# ESP_IAQ_baseBoard.net
KiCad netlist of a schematic drawn in EAGLE
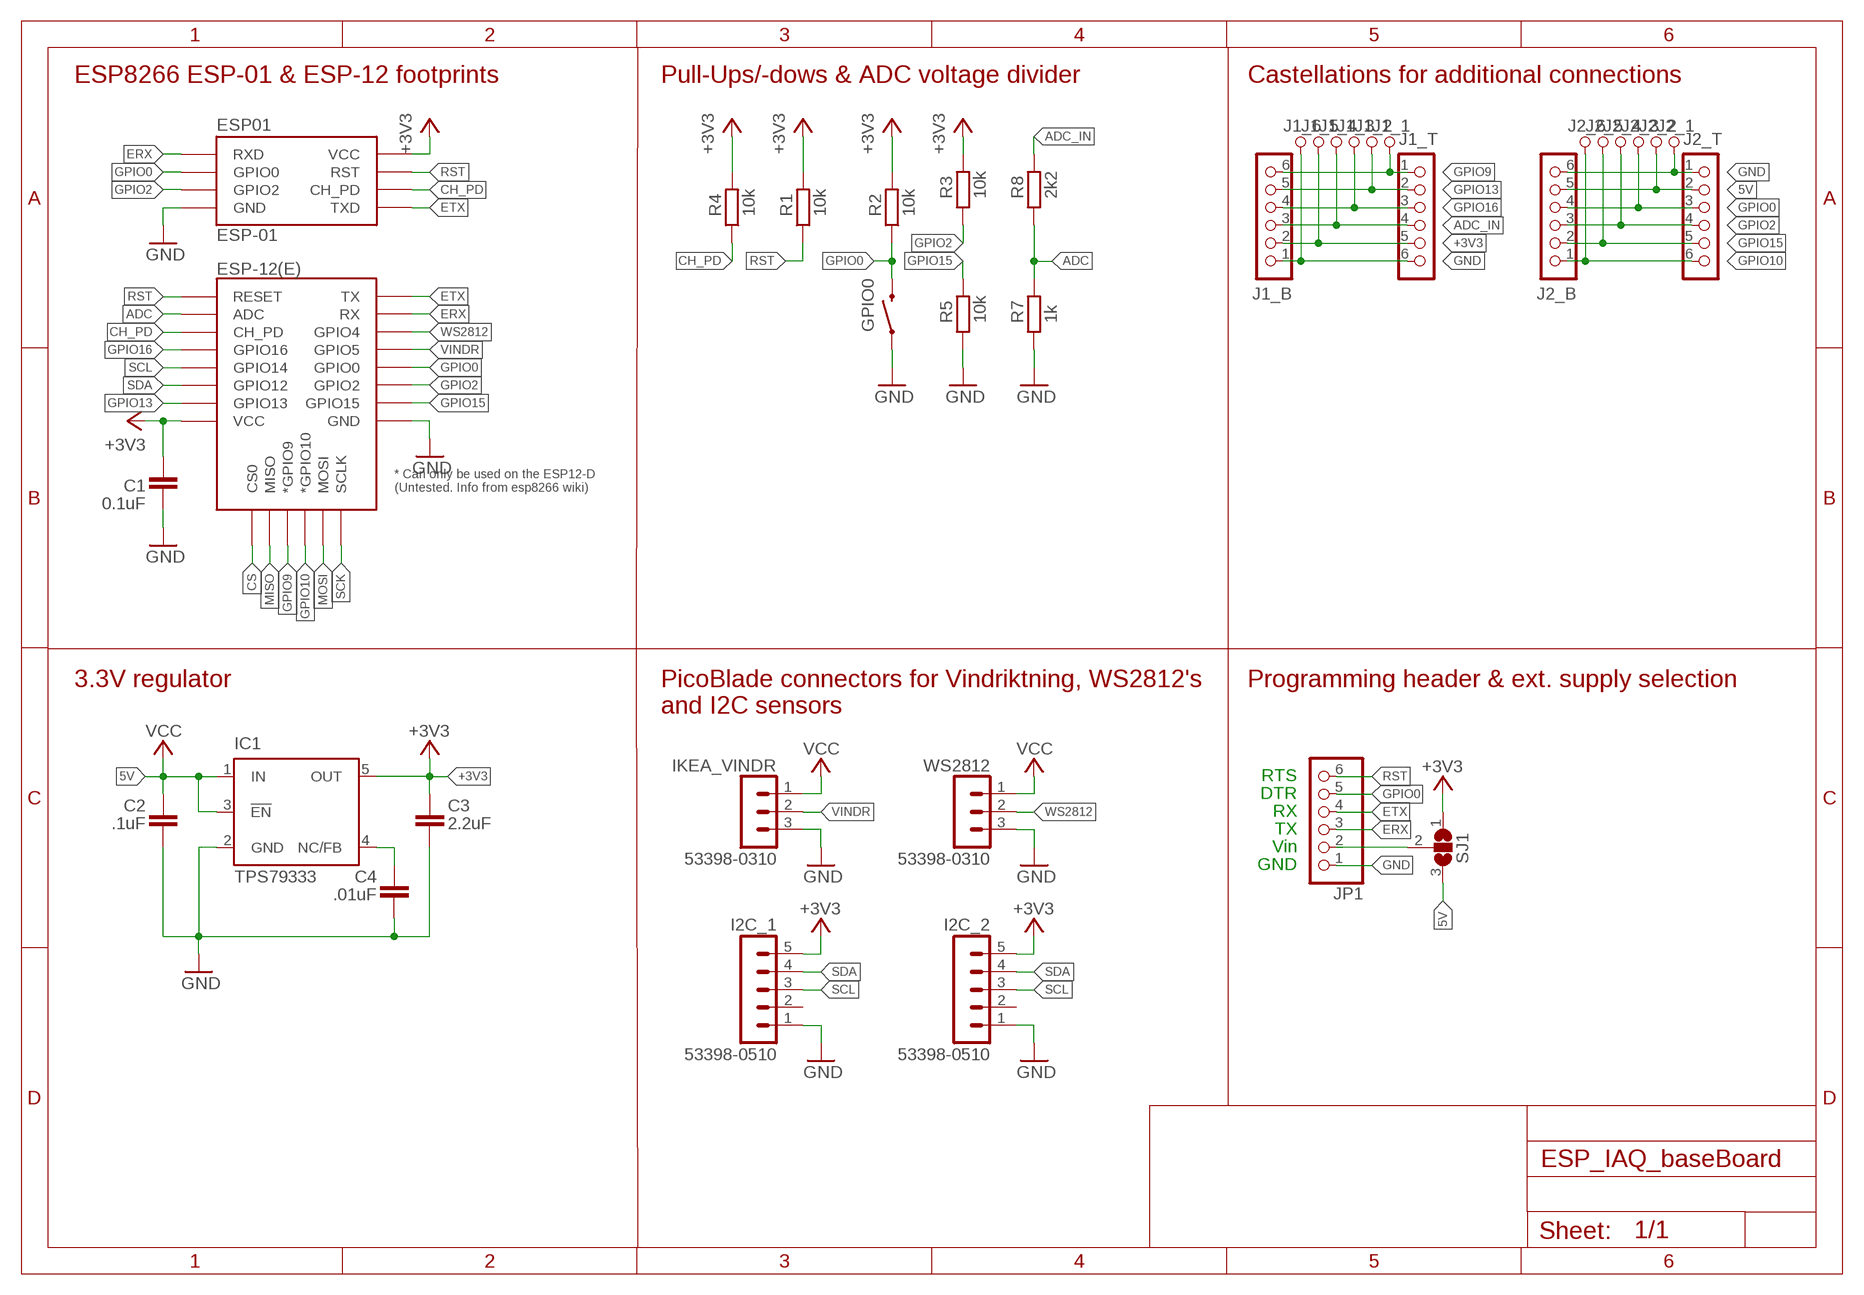
[diagram p0: schematic, sheet 1]

(export (version "E")
  (design (tool "Eeschema 10.0.6"))
  (components
    (comp (ref "C1")
      (value "0.1uF")
      (footprint "eagle-import:C805")
      (libsource (lib "eagle-import") (part "CAPACITOR_NPOL-0805"))
    )
    (comp (ref "C2")
      (value ".1uF")
      (footprint "eagle-import:C805")
      (libsource (lib "eagle-import") (part "CAPACITOR_NPOL-0805"))
    )
    (comp (ref "C3")
      (value "2.2uF")
      (footprint "eagle-import:C805")
      (libsource (lib "eagle-import") (part "CAPACITOR_NPOL-0805"))
    )
    (comp (ref "C4")
      (value ".01uF")
      (footprint "eagle-import:C805")
      (libsource (lib "eagle-import") (part "CAPACITOR_NPOL-0805"))
    )
    (comp (ref "ESP-01")
      (value "ESP01")
      (footprint "eagle-import:ESP01")
      (libsource (lib "eagle-import") (part "ESP01"))
    )
    (comp (ref "ESP-12(E)")
      (value "ESP12ESMD")
      (footprint "eagle-import:ESP12E-SMD")
      (libsource (lib "eagle-import") (part "ESP12ESMD"))
    )
    (comp (ref "GPIO0")
      (value "MOMENTARY-SWITCH-SPST-SMD-RIGHT-ANGLE")
      (footprint "eagle-import:TACTILE_SWITCH_SMD_RIGHT_ANGLE")
      (libsource (lib "eagle-import") (part "MOMENTARY-SWITCH-SPST-SMD-RIGHT-ANGLE"))
    )
    (comp (ref "I2C_1")
      (value "53398-0510")
      (footprint "eagle-import:53398-0510")
      (libsource (lib "eagle-import") (part "53398-0510"))
    )
    (comp (ref "I2C_2")
      (value "53398-0510")
      (footprint "eagle-import:53398-0510")
      (libsource (lib "eagle-import") (part "53398-0510"))
    )
    (comp (ref "IC1")
      (value "TPS79333")
      (footprint "eagle-import:SOT23-DBV")
      (fields (field (name "MF") "TEXAS INSTRUMENTS") (field (name "MPN") "TPS77033DBVT"))
      (libsource (lib "eagle-import") (part "TPS77033"))
    )
    (comp (ref "IKEA_VINDR")
      (value "53398-0310")
      (footprint "eagle-import:53398-0310")
      (libsource (lib "eagle-import") (part "53398-0310"))
    )
    (comp (ref "J1_1")
      (value "PAD_TERMINAL-1.02MM_ROUND")
      (footprint "eagle-import:CON_PAD_ROUND_1.02MM")
      (libsource (lib "eagle-import") (part "PAD_TERMINAL-1.02MM_ROUND"))
    )
    (comp (ref "J1_2")
      (value "PAD_TERMINAL-1.02MM_ROUND")
      (footprint "eagle-import:CON_PAD_ROUND_1.02MM")
      (libsource (lib "eagle-import") (part "PAD_TERMINAL-1.02MM_ROUND"))
    )
    (comp (ref "J1_3")
      (value "PAD_TERMINAL-1.02MM_ROUND")
      (footprint "eagle-import:CON_PAD_ROUND_1.02MM")
      (libsource (lib "eagle-import") (part "PAD_TERMINAL-1.02MM_ROUND"))
    )
    (comp (ref "J1_4")
      (value "PAD_TERMINAL-1.02MM_ROUND")
      (footprint "eagle-import:CON_PAD_ROUND_1.02MM")
      (libsource (lib "eagle-import") (part "PAD_TERMINAL-1.02MM_ROUND"))
    )
    (comp (ref "J1_5")
      (value "PAD_TERMINAL-1.02MM_ROUND")
      (footprint "eagle-import:CON_PAD_ROUND_1.02MM")
      (libsource (lib "eagle-import") (part "PAD_TERMINAL-1.02MM_ROUND"))
    )
    (comp (ref "J1_6")
      (value "PAD_TERMINAL-1.02MM_ROUND")
      (footprint "eagle-import:CON_PAD_ROUND_1.02MM")
      (libsource (lib "eagle-import") (part "PAD_TERMINAL-1.02MM_ROUND"))
    )
    (comp (ref "J1_B")
      (value "CON_HEADER_1X06-SMD-RIGHT-ANGLED")
      (footprint "eagle-import:M1X6_MALE_RIGHT_ANGLED_SMD")
      (libsource (lib "eagle-import") (part "CON_HEADER_1X06-SMD-RIGHT-ANGLED"))
    )
    (comp (ref "J1_T")
      (value "CON_HEADER_1X06-SMD-RIGHT-ANGLED")
      (footprint "eagle-import:M1X6_MALE_RIGHT_ANGLED_SMD")
      (libsource (lib "eagle-import") (part "CON_HEADER_1X06-SMD-RIGHT-ANGLED"))
    )
    (comp (ref "J2_1")
      (value "PAD_TERMINAL-1.02MM_ROUND")
      (footprint "eagle-import:CON_PAD_ROUND_1.02MM")
      (libsource (lib "eagle-import") (part "PAD_TERMINAL-1.02MM_ROUND"))
    )
    (comp (ref "J2_2")
      (value "PAD_TERMINAL-1.02MM_ROUND")
      (footprint "eagle-import:CON_PAD_ROUND_1.02MM")
      (libsource (lib "eagle-import") (part "PAD_TERMINAL-1.02MM_ROUND"))
    )
    (comp (ref "J2_3")
      (value "PAD_TERMINAL-1.02MM_ROUND")
      (footprint "eagle-import:CON_PAD_ROUND_1.02MM")
      (libsource (lib "eagle-import") (part "PAD_TERMINAL-1.02MM_ROUND"))
    )
    (comp (ref "J2_4")
      (value "PAD_TERMINAL-1.02MM_ROUND")
      (footprint "eagle-import:CON_PAD_ROUND_1.02MM")
      (libsource (lib "eagle-import") (part "PAD_TERMINAL-1.02MM_ROUND"))
    )
    (comp (ref "J2_5")
      (value "PAD_TERMINAL-1.02MM_ROUND")
      (footprint "eagle-import:CON_PAD_ROUND_1.02MM")
      (libsource (lib "eagle-import") (part "PAD_TERMINAL-1.02MM_ROUND"))
    )
    (comp (ref "J2_6")
      (value "PAD_TERMINAL-1.02MM_ROUND")
      (footprint "eagle-import:CON_PAD_ROUND_1.02MM")
      (libsource (lib "eagle-import") (part "PAD_TERMINAL-1.02MM_ROUND"))
    )
    (comp (ref "J2_B")
      (value "CON_HEADER_1X06-SMD-RIGHT-ANGLED")
      (footprint "eagle-import:M1X6_MALE_RIGHT_ANGLED_SMD")
      (libsource (lib "eagle-import") (part "CON_HEADER_1X06-SMD-RIGHT-ANGLED"))
    )
    (comp (ref "J2_T")
      (value "CON_HEADER_1X06-SMD-RIGHT-ANGLED")
      (footprint "eagle-import:M1X6_MALE_RIGHT_ANGLED_SMD")
      (libsource (lib "eagle-import") (part "CON_HEADER_1X06-SMD-RIGHT-ANGLED"))
    )
    (comp (ref "JP1")
      (value "PINHD-1X6LOCK")
      (footprint "eagle-import:1X06-BIGLOCK")
      (libsource (lib "eagle-import") (part "PINHD-1X6LOCK"))
    )
    (comp (ref "R1")
      (value "10k")
      (footprint "eagle-import:R603")
      (libsource (lib "eagle-import") (part "RESISTOR-0603"))
    )
    (comp (ref "R2")
      (value "10k")
      (footprint "eagle-import:R603")
      (libsource (lib "eagle-import") (part "RESISTOR-0603"))
    )
    (comp (ref "R3")
      (value "10k")
      (footprint "eagle-import:R603")
      (libsource (lib "eagle-import") (part "RESISTOR-0603"))
    )
    (comp (ref "R4")
      (value "10k")
      (footprint "eagle-import:R603")
      (libsource (lib "eagle-import") (part "RESISTOR-0603"))
    )
    (comp (ref "R5")
      (value "10k")
      (footprint "eagle-import:R603")
      (libsource (lib "eagle-import") (part "RESISTOR-0603"))
    )
    (comp (ref "R7")
      (value "1k")
      (footprint "eagle-import:R603")
      (libsource (lib "eagle-import") (part "RESISTOR-0603"))
    )
    (comp (ref "R8")
      (value "2k2")
      (footprint "eagle-import:R603")
      (libsource (lib "eagle-import") (part "RESISTOR-0603"))
    )
    (comp (ref "SJ1")
      (value "SJ2W")
      (footprint "eagle-import:SJ_2")
      (libsource (lib "eagle-import") (part "SJ2W"))
    )
    (comp (ref "WS2812")
      (value "53398-0310")
      (footprint "eagle-import:53398-0310")
      (libsource (lib "eagle-import") (part "53398-0310"))
    )
  )
  (nets
    (net (code "1") (name "+3V3") (class "Default")
      (node (ref "C1") (pin "1") (pinfunction "1_1") (pintype "passive"))
      (node (ref "C3") (pin "1") (pinfunction "1_1") (pintype "passive"))
      (node (ref "ESP-01") (pin "VCC") (pinfunction "VCC_VCC") (pintype "bidirectional"))
      (node (ref "ESP-12(E)") (pin "VCC") (pinfunction "VCC_VCC") (pintype "bidirectional"))
      (node (ref "I2C_1") (pin "5") (pinfunction "5_5") (pintype "passive"))
      (node (ref "I2C_2") (pin "5") (pinfunction "5_5") (pintype "passive"))
      (node (ref "IC1") (pin "5") (pinfunction "OUT_5") (pintype "passive"))
      (node (ref "J1_5") (pin "P") (pinfunction "P_P") (pintype "passive"))
      (node (ref "J1_B") (pin "2") (pinfunction "2_2") (pintype "bidirectional"))
      (node (ref "J1_T") (pin "5") (pinfunction "5_5") (pintype "passive"))
      (node (ref "R1") (pin "2") (pinfunction "2_2") (pintype "passive"))
      (node (ref "R2") (pin "2") (pinfunction "2_2") (pintype "passive"))
      (node (ref "R3") (pin "2") (pinfunction "2_2") (pintype "passive"))
      (node (ref "R4") (pin "2") (pinfunction "2_2") (pintype "passive"))
      (node (ref "SJ1") (pin "1") (pinfunction "1_1") (pintype "passive"))
    )
    (net (code "2") (name "5V") (class "Default")
      (node (ref "C2") (pin "1") (pinfunction "1_1") (pintype "passive"))
      (node (ref "IC1") (pin "1") (pinfunction "IN_1") (pintype "input"))
      (node (ref "IC1") (pin "3") (pinfunction "~{EN}_3") (pintype "input"))
      (node (ref "IKEA_VINDR") (pin "1") (pinfunction "1_1") (pintype "passive"))
      (node (ref "J2_2") (pin "P") (pinfunction "P_P") (pintype "passive"))
      (node (ref "J2_B") (pin "5") (pinfunction "5_5") (pintype "passive"))
      (node (ref "J2_T") (pin "2") (pinfunction "2_2") (pintype "bidirectional"))
      (node (ref "SJ1") (pin "3") (pinfunction "3_3") (pintype "passive"))
      (node (ref "WS2812") (pin "1") (pinfunction "1_1") (pintype "passive"))
    )
    (net (code "3") (name "ADC") (class "Default")
      (node (ref "ESP-12(E)") (pin "ADC") (pinfunction "ADC_ADC") (pintype "bidirectional"))
      (node (ref "R7") (pin "2") (pinfunction "2_2") (pintype "passive"))
      (node (ref "R8") (pin "1") (pinfunction "1_1") (pintype "passive"))
    )
    (net (code "4") (name "ADC_IN") (class "Default")
      (node (ref "J1_4") (pin "P") (pinfunction "P_P") (pintype "passive"))
      (node (ref "J1_B") (pin "3") (pinfunction "3_3") (pintype "passive"))
      (node (ref "J1_T") (pin "4") (pinfunction "4_4") (pintype "passive"))
      (node (ref "R8") (pin "2") (pinfunction "2_2") (pintype "passive"))
    )
    (net (code "5") (name "CH_PD") (class "Default")
      (node (ref "ESP-01") (pin "CH_PD") (pinfunction "CH_PD_CH_PD") (pintype "bidirectional"))
      (node (ref "ESP-12(E)") (pin "CH_PD") (pinfunction "CH_PD_CH_PD") (pintype "bidirectional"))
      (node (ref "R4") (pin "1") (pinfunction "1_1") (pintype "passive"))
    )
    (net (code "6") (name "CS") (class "Default")
      (node (ref "ESP-12(E)") (pin "CS0") (pinfunction "CS0_CS0") (pintype "bidirectional"))
    )
    (net (code "7") (name "ERX") (class "Default")
      (node (ref "ESP-01") (pin "RX") (pinfunction "RXD_RX") (pintype "bidirectional"))
      (node (ref "ESP-12(E)") (pin "RXD0") (pinfunction "RX_RXD0") (pintype "bidirectional"))
      (node (ref "JP1") (pin "3") (pinfunction "3_3") (pintype "passive"))
    )
    (net (code "8") (name "ETX") (class "Default")
      (node (ref "ESP-01") (pin "TX") (pinfunction "TXD_TX") (pintype "bidirectional"))
      (node (ref "ESP-12(E)") (pin "TXD0") (pinfunction "TX_TXD0") (pintype "bidirectional"))
      (node (ref "JP1") (pin "4") (pinfunction "4_4") (pintype "passive"))
    )
    (net (code "9") (name "GND") (class "Default")
      (node (ref "C1") (pin "2") (pinfunction "2_2") (pintype "passive"))
      (node (ref "C2") (pin "2") (pinfunction "2_2") (pintype "passive"))
      (node (ref "C3") (pin "2") (pinfunction "2_2") (pintype "passive"))
      (node (ref "C4") (pin "2") (pinfunction "2_2") (pintype "passive"))
      (node (ref "ESP-01") (pin "GND") (pinfunction "GND_GND") (pintype "bidirectional"))
      (node (ref "ESP-12(E)") (pin "GND") (pinfunction "GND_GND") (pintype "bidirectional"))
      (node (ref "GPIO0") (pin "1") (pinfunction "1_1") (pintype "passive"))
      (node (ref "I2C_1") (pin "1") (pinfunction "1_1") (pintype "passive"))
      (node (ref "I2C_2") (pin "1") (pinfunction "1_1") (pintype "passive"))
      (node (ref "IC1") (pin "2") (pinfunction "GND_2") (pintype "power_in"))
      (node (ref "IKEA_VINDR") (pin "3") (pinfunction "3_3") (pintype "passive"))
      (node (ref "J1_6") (pin "P") (pinfunction "P_P") (pintype "passive"))
      (node (ref "J1_B") (pin "1") (pinfunction "1_1") (pintype "bidirectional"))
      (node (ref "J1_T") (pin "6") (pinfunction "6_6") (pintype "passive"))
      (node (ref "J2_1") (pin "P") (pinfunction "P_P") (pintype "passive"))
      (node (ref "J2_B") (pin "6") (pinfunction "6_6") (pintype "passive"))
      (node (ref "J2_T") (pin "1") (pinfunction "1_1") (pintype "bidirectional"))
      (node (ref "JP1") (pin "1") (pinfunction "1_1") (pintype "passive"))
      (node (ref "R5") (pin "1") (pinfunction "1_1") (pintype "passive"))
      (node (ref "R7") (pin "1") (pinfunction "1_1") (pintype "passive"))
      (node (ref "WS2812") (pin "3") (pinfunction "3_3") (pintype "passive"))
    )
    (net (code "10") (name "GPIO0") (class "Default")
      (node (ref "ESP-01") (pin "GPIO0") (pinfunction "GPIO0_GPIO0") (pintype "bidirectional"))
      (node (ref "ESP-12(E)") (pin "GPIO0") (pinfunction "GPIO0_GPIO0") (pintype "bidirectional"))
      (node (ref "GPIO0") (pin "2") (pinfunction "2_2") (pintype "passive"))
      (node (ref "J2_3") (pin "P") (pinfunction "P_P") (pintype "passive"))
      (node (ref "J2_B") (pin "4") (pinfunction "4_4") (pintype "passive"))
      (node (ref "J2_T") (pin "3") (pinfunction "3_3") (pintype "passive"))
      (node (ref "JP1") (pin "5") (pinfunction "5_5") (pintype "passive"))
      (node (ref "R2") (pin "1") (pinfunction "1_1") (pintype "passive"))
    )
    (net (code "11") (name "GPIO2") (class "Default")
      (node (ref "ESP-01") (pin "GPIO2") (pinfunction "GPIO2_GPIO2") (pintype "bidirectional"))
      (node (ref "ESP-12(E)") (pin "GPIO2") (pinfunction "GPIO2_GPIO2") (pintype "bidirectional"))
      (node (ref "J2_4") (pin "P") (pinfunction "P_P") (pintype "passive"))
      (node (ref "J2_B") (pin "3") (pinfunction "3_3") (pintype "passive"))
      (node (ref "J2_T") (pin "4") (pinfunction "4_4") (pintype "passive"))
      (node (ref "R3") (pin "1") (pinfunction "1_1") (pintype "passive"))
    )
    (net (code "12") (name "GPIO9") (class "Default")
      (node (ref "ESP-12(E)") (pin "GPIO9") (pinfunction "*GPIO9_GPIO9") (pintype "bidirectional"))
      (node (ref "J1_1") (pin "P") (pinfunction "P_P") (pintype "passive"))
      (node (ref "J1_B") (pin "6") (pinfunction "6_6") (pintype "passive"))
      (node (ref "J1_T") (pin "1") (pinfunction "1_1") (pintype "bidirectional"))
    )
    (net (code "13") (name "GPIO10") (class "Default")
      (node (ref "ESP-12(E)") (pin "GPIO10") (pinfunction "*GPIO10_GPIO10") (pintype "bidirectional"))
      (node (ref "J2_6") (pin "P") (pinfunction "P_P") (pintype "passive"))
      (node (ref "J2_B") (pin "1") (pinfunction "1_1") (pintype "bidirectional"))
      (node (ref "J2_T") (pin "6") (pinfunction "6_6") (pintype "passive"))
    )
    (net (code "14") (name "GPIO13") (class "Default")
      (node (ref "ESP-12(E)") (pin "GPIO13") (pinfunction "GPIO13_GPIO13") (pintype "bidirectional"))
      (node (ref "J1_2") (pin "P") (pinfunction "P_P") (pintype "passive"))
      (node (ref "J1_B") (pin "5") (pinfunction "5_5") (pintype "passive"))
      (node (ref "J1_T") (pin "2") (pinfunction "2_2") (pintype "bidirectional"))
    )
    (net (code "15") (name "GPIO15") (class "Default")
      (node (ref "ESP-12(E)") (pin "GPIO15") (pinfunction "GPIO15_GPIO15") (pintype "bidirectional"))
      (node (ref "J2_5") (pin "P") (pinfunction "P_P") (pintype "passive"))
      (node (ref "J2_B") (pin "2") (pinfunction "2_2") (pintype "bidirectional"))
      (node (ref "J2_T") (pin "5") (pinfunction "5_5") (pintype "passive"))
      (node (ref "R5") (pin "2") (pinfunction "2_2") (pintype "passive"))
    )
    (net (code "16") (name "GPIO16") (class "Default")
      (node (ref "ESP-12(E)") (pin "GPIO16") (pinfunction "GPIO16_GPIO16") (pintype "bidirectional"))
      (node (ref "J1_3") (pin "P") (pinfunction "P_P") (pintype "passive"))
      (node (ref "J1_B") (pin "4") (pinfunction "4_4") (pintype "passive"))
      (node (ref "J1_T") (pin "3") (pinfunction "3_3") (pintype "passive"))
    )
    (net (code "17") (name "MISO") (class "Default")
      (node (ref "ESP-12(E)") (pin "MISO") (pinfunction "MISO_MISO") (pintype "bidirectional"))
    )
    (net (code "18") (name "MOSI") (class "Default")
      (node (ref "ESP-12(E)") (pin "MOSI") (pinfunction "MOSI_MOSI") (pintype "bidirectional"))
    )
    (net (code "19") (name "Net-(IC1-NC{slash}FB)") (class "Default")
      (node (ref "C4") (pin "1") (pinfunction "1_1") (pintype "passive"))
      (node (ref "IC1") (pin "4") (pinfunction "NC/FB_4") (pintype "passive"))
    )
    (net (code "20") (name "Net-(JP1-Pad2)") (class "Default")
      (node (ref "JP1") (pin "2") (pinfunction "2_2") (pintype "passive"))
      (node (ref "SJ1") (pin "2") (pinfunction "2_2") (pintype "passive"))
    )
    (net (code "21") (name "RST") (class "Default")
      (node (ref "ESP-01") (pin "RST") (pinfunction "RST_RST") (pintype "bidirectional"))
      (node (ref "ESP-12(E)") (pin "RESET") (pinfunction "RESET_RESET") (pintype "bidirectional"))
      (node (ref "JP1") (pin "6") (pinfunction "6_6") (pintype "passive"))
      (node (ref "R1") (pin "1") (pinfunction "1_1") (pintype "passive"))
    )
    (net (code "22") (name "SCK") (class "Default")
      (node (ref "ESP-12(E)") (pin "SCLK") (pinfunction "SCLK_SCLK") (pintype "bidirectional"))
    )
    (net (code "23") (name "SCL") (class "Default")
      (node (ref "ESP-12(E)") (pin "GPIO14") (pinfunction "GPIO14_GPIO14") (pintype "bidirectional"))
      (node (ref "I2C_1") (pin "3") (pinfunction "3_3") (pintype "passive"))
      (node (ref "I2C_2") (pin "3") (pinfunction "3_3") (pintype "passive"))
    )
    (net (code "24") (name "SDA") (class "Default")
      (node (ref "ESP-12(E)") (pin "GPIO12") (pinfunction "GPIO12_GPIO12") (pintype "bidirectional"))
      (node (ref "I2C_1") (pin "4") (pinfunction "4_4") (pintype "passive"))
      (node (ref "I2C_2") (pin "4") (pinfunction "4_4") (pintype "passive"))
    )
    (net (code "25") (name "VINDR") (class "Default")
      (node (ref "ESP-12(E)") (pin "GPIO5") (pinfunction "GPIO5_GPIO5") (pintype "bidirectional"))
      (node (ref "IKEA_VINDR") (pin "2") (pinfunction "2_2") (pintype "passive"))
    )
    (net (code "26") (name "WS2812") (class "Default")
      (node (ref "ESP-12(E)") (pin "GPIO4") (pinfunction "GPIO4_GPIO4") (pintype "bidirectional"))
      (node (ref "WS2812") (pin "2") (pinfunction "2_2") (pintype "passive"))
    )
    (net (code "27") (name "unconnected-(I2C_1-Pad2)") (class "Default")
      (node (ref "I2C_1") (pin "2") (pinfunction "2_2") (pintype "passive"))
    )
    (net (code "28") (name "unconnected-(I2C_2-Pad2)") (class "Default")
      (node (ref "I2C_2") (pin "2") (pinfunction "2_2") (pintype "passive"))
    )
  )
)
